# 141004_AriloTX_REV3_1_0_433MHZ_td.net
KiCad netlist of a schematic drawn in EAGLE
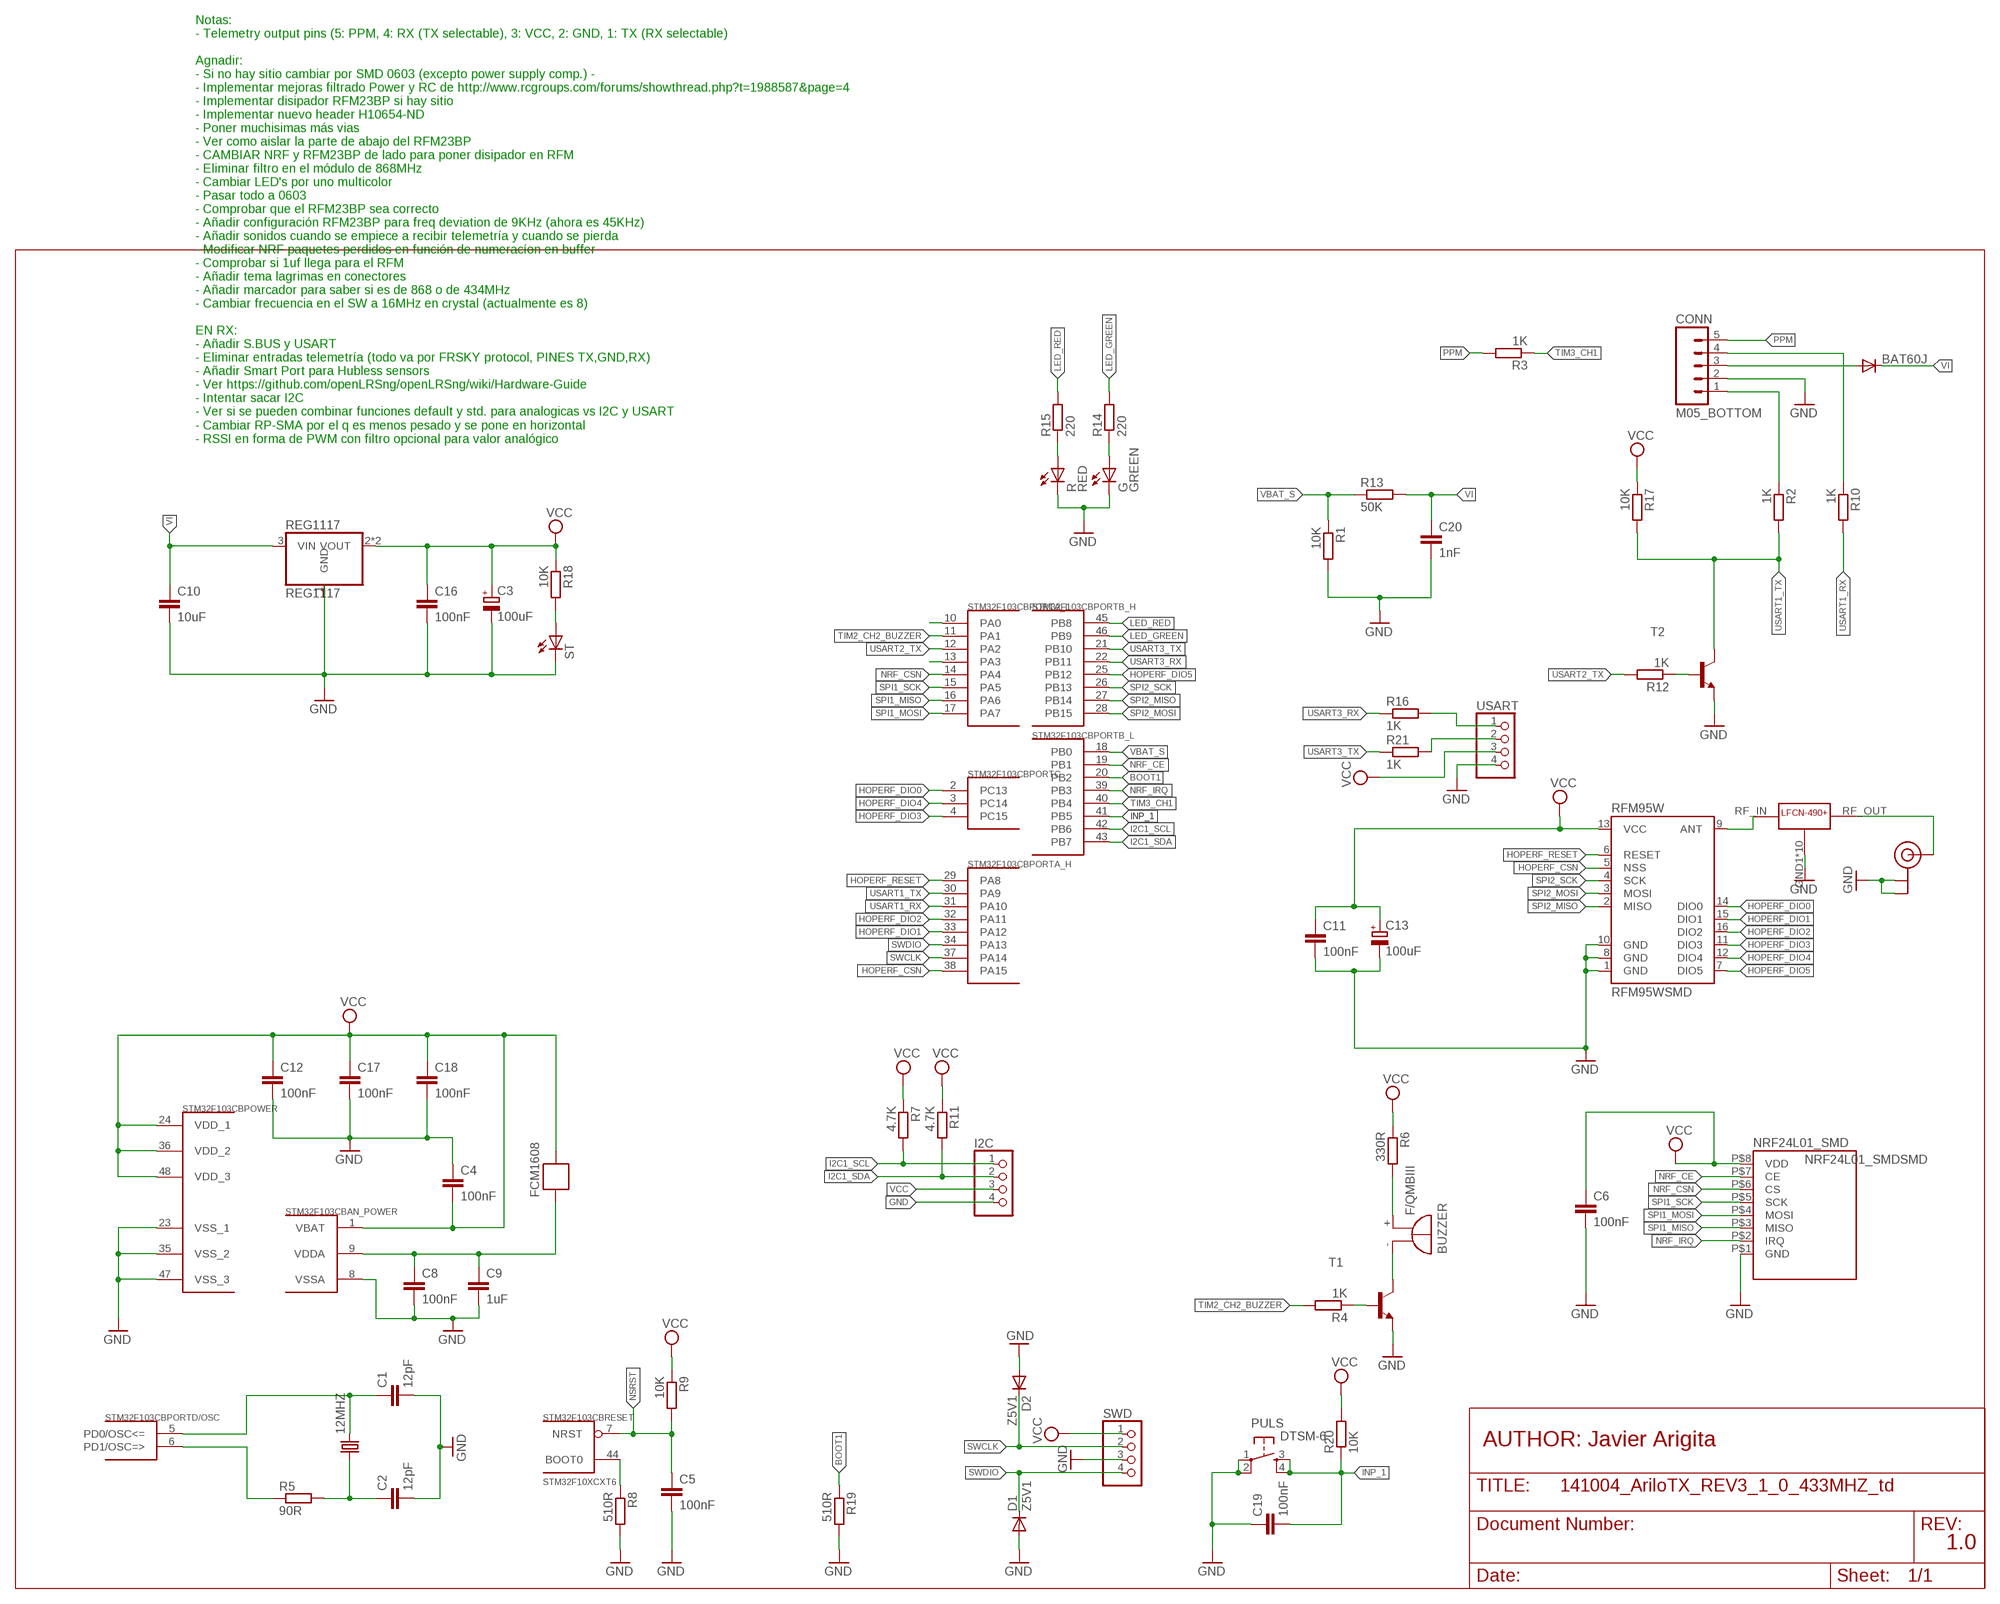
[diagram p0: schematic, sheet 1]

(export (version "E")
  (design (tool "Eeschema 10.0.6"))
  (components
    (comp (ref "12MHZ")
      (value "CRYSTAL5X3")
      (footprint "eagle-import:CRYSTAL-SMD-5X3")
      (libsource (lib "eagle-import") (part "CRYSTAL5X3"))
    )
    (comp (ref "BAT60J")
      (value "DIODE-SOD323-R")
      (footprint "eagle-import:SOD323-R")
      (libsource (lib "eagle-import") (part "DIODE-SOD323-R"))
    )
    (comp (ref "BUZZER")
      (value "F/QMBIII")
      (footprint "eagle-import:F_QMBIII")
      (libsource (lib "eagle-import") (part "F/QMBIII"))
    )
    (comp (ref "C1")
      (value "12pF")
      (footprint "eagle-import:C0603")
      (libsource (lib "eagle-import") (part "C-EUC0603"))
    )
    (comp (ref "C2")
      (value "12pF")
      (footprint "eagle-import:C0603")
      (libsource (lib "eagle-import") (part "C-EUC0603"))
    )
    (comp (ref "C3")
      (value "100uF")
      (footprint "eagle-import:SMC_B")
      (libsource (lib "eagle-import") (part "CPOL-EUSMCB"))
    )
    (comp (ref "C4")
      (value "100nF")
      (footprint "eagle-import:C0603")
      (libsource (lib "eagle-import") (part "C-EUC0603"))
    )
    (comp (ref "C5")
      (value "100nF")
      (footprint "eagle-import:C0603")
      (libsource (lib "eagle-import") (part "C-EUC0603"))
    )
    (comp (ref "C6")
      (value "100nF")
      (footprint "eagle-import:C0603")
      (libsource (lib "eagle-import") (part "C-EUC0603"))
    )
    (comp (ref "C8")
      (value "100nF")
      (footprint "eagle-import:C0603")
      (libsource (lib "eagle-import") (part "C-EUC0603"))
    )
    (comp (ref "C9")
      (value "1uF")
      (footprint "eagle-import:C0603")
      (libsource (lib "eagle-import") (part "C-EUC0603"))
    )
    (comp (ref "C10")
      (value "10uF")
      (footprint "eagle-import:C3216")
      (libsource (lib "eagle-import") (part "resistor_C-EUC3216"))
    )
    (comp (ref "C11")
      (value "100nF")
      (footprint "eagle-import:C0603")
      (libsource (lib "eagle-import") (part "C-EUC0603"))
    )
    (comp (ref "C12")
      (value "100nF")
      (footprint "eagle-import:C0603")
      (libsource (lib "eagle-import") (part "C-EUC0603"))
    )
    (comp (ref "C13")
      (value "100uF")
      (footprint "eagle-import:SMC_B")
      (libsource (lib "eagle-import") (part "CPOL-EUSMCB"))
    )
    (comp (ref "C16")
      (value "100nF")
      (footprint "eagle-import:C0603")
      (libsource (lib "eagle-import") (part "C-EUC0603"))
    )
    (comp (ref "C17")
      (value "100nF")
      (footprint "eagle-import:C0603")
      (libsource (lib "eagle-import") (part "C-EUC0603"))
    )
    (comp (ref "C18")
      (value "100nF")
      (footprint "eagle-import:C0603")
      (libsource (lib "eagle-import") (part "C-EUC0603"))
    )
    (comp (ref "C19")
      (value "100nF")
      (footprint "eagle-import:C0603")
      (libsource (lib "eagle-import") (part "C-EUC0603"))
    )
    (comp (ref "C20")
      (value "1nF")
      (footprint "eagle-import:C0603")
      (libsource (lib "eagle-import") (part "C-EUC0603"))
    )
    (comp (ref "CONN")
      (value "M05_BOTTOM")
      (footprint "eagle-import:M05_BOTTOM")
      (libsource (lib "eagle-import") (part "M05_BOTTOM"))
    )
    (comp (ref "D1")
      (value "Z5V1")
      (footprint "eagle-import:SOD323-R")
      (libsource (lib "eagle-import") (part "DIODE-SOD323-R"))
    )
    (comp (ref "D2")
      (value "Z5V1")
      (footprint "eagle-import:SOD323-R")
      (libsource (lib "eagle-import") (part "DIODE-SOD323-R"))
    )
    (comp (ref "FCM1608")
      (value "FERRITE-BEAD")
      (footprint "eagle-import:R0603")
      (libsource (lib "eagle-import") (part "FERRITE-BEAD"))
    )
    (comp (ref "G")
      (value "GREEN")
      (footprint "eagle-import:CHIP-LED0603")
      (libsource (lib "eagle-import") (part "LEDCHIP-LED0603"))
    )
    (comp (ref "I2C")
      (value "PINHD-1X4")
      (footprint "eagle-import:1X04")
      (libsource (lib "eagle-import") (part "PINHD-1X4"))
    )
    (comp (ref "LFCN490+")
      (value "LFCN490+")
      (footprint "eagle-import:LFCN490+")
      (libsource (lib "eagle-import") (part "LFCN490+"))
    )
    (comp (ref "NRF24L01_SMD")
      (value "NRF24L01_SMDSMD")
      (footprint "eagle-import:NRF24L01_SMD")
      (libsource (lib "eagle-import") (part "NRF24L01_SMDSMD"))
    )
    (comp (ref "PULS")
      (value "DTSM-6")
      (footprint "eagle-import:DTSM-6")
      (libsource (lib "eagle-import") (part "DTSM-6"))
    )
    (comp (ref "R")
      (value "RED")
      (footprint "eagle-import:CHIP-LED0603")
      (libsource (lib "eagle-import") (part "LEDCHIP-LED0603"))
    )
    (comp (ref "R1")
      (value "10K")
      (footprint "eagle-import:R0603")
      (libsource (lib "eagle-import") (part "R-EU_R0603"))
    )
    (comp (ref "R2")
      (value "1K")
      (footprint "eagle-import:R0603")
      (libsource (lib "eagle-import") (part "R-EU_R0603"))
    )
    (comp (ref "R3")
      (value "1K")
      (footprint "eagle-import:R0603")
      (libsource (lib "eagle-import") (part "R-EU_R0603"))
    )
    (comp (ref "R4")
      (value "1K")
      (footprint "eagle-import:R0603")
      (libsource (lib "eagle-import") (part "R-EU_R0603"))
    )
    (comp (ref "R5")
      (value "90R")
      (footprint "eagle-import:R0603")
      (libsource (lib "eagle-import") (part "R-EU_R0603"))
    )
    (comp (ref "R6")
      (value "330R")
      (footprint "eagle-import:R0603")
      (libsource (lib "eagle-import") (part "R-EU_R0603"))
    )
    (comp (ref "R7")
      (value "4.7K")
      (footprint "eagle-import:R0603")
      (libsource (lib "eagle-import") (part "R-EU_R0603"))
    )
    (comp (ref "R8")
      (value "510R")
      (footprint "eagle-import:R0603")
      (libsource (lib "eagle-import") (part "R-EU_R0603"))
    )
    (comp (ref "R9")
      (value "10K")
      (footprint "eagle-import:R0603")
      (libsource (lib "eagle-import") (part "R-EU_R0603"))
    )
    (comp (ref "R10")
      (value "1K")
      (footprint "eagle-import:R0603")
      (libsource (lib "eagle-import") (part "R-EU_R0603"))
    )
    (comp (ref "R11")
      (value "4.7K")
      (footprint "eagle-import:R0603")
      (libsource (lib "eagle-import") (part "R-EU_R0603"))
    )
    (comp (ref "R12")
      (value "1K")
      (footprint "eagle-import:R0603")
      (libsource (lib "eagle-import") (part "R-EU_R0603"))
    )
    (comp (ref "R13")
      (value "50K")
      (footprint "eagle-import:R0603")
      (libsource (lib "eagle-import") (part "R-EU_R0603"))
    )
    (comp (ref "R14")
      (value "220")
      (footprint "eagle-import:R0603")
      (libsource (lib "eagle-import") (part "R-EU_R0603"))
    )
    (comp (ref "R15")
      (value "220")
      (footprint "eagle-import:R0603")
      (libsource (lib "eagle-import") (part "R-EU_R0603"))
    )
    (comp (ref "R16")
      (value "1K")
      (footprint "eagle-import:R0603")
      (libsource (lib "eagle-import") (part "R-EU_R0603"))
    )
    (comp (ref "R17")
      (value "10K")
      (footprint "eagle-import:R0603")
      (libsource (lib "eagle-import") (part "R-EU_R0603"))
    )
    (comp (ref "R18")
      (value "10K")
      (footprint "eagle-import:R0603")
      (libsource (lib "eagle-import") (part "R-EU_R0603"))
    )
    (comp (ref "R19")
      (value "510R")
      (footprint "eagle-import:R0603")
      (libsource (lib "eagle-import") (part "R-EU_R0603"))
    )
    (comp (ref "R20")
      (value "10K")
      (footprint "eagle-import:R0603")
      (libsource (lib "eagle-import") (part "R-EU_R0603"))
    )
    (comp (ref "R21")
      (value "1K")
      (footprint "eagle-import:R0603")
      (libsource (lib "eagle-import") (part "R-EU_R0603"))
    )
    (comp (ref "REG1117")
      (value "REG1117")
      (footprint "eagle-import:SOT223")
      (libsource (lib "eagle-import") (part "REG1117"))
    )
    (comp (ref "RFM95W")
      (value "RFM95WSMD")
      (footprint "eagle-import:MISIEK_RFM95W_SMD")
      (libsource (lib "eagle-import") (part "MISIEK_RFM95WSMD"))
    )
    (comp (ref "ST")
      (value "LEDCHIP-LED0603")
      (footprint "eagle-import:CHIP-LED0603")
      (libsource (lib "eagle-import") (part "LEDCHIP-LED0603"))
    )
    (comp (ref "STM32F103CB")
      (value "STM32F10XCXT6")
      (footprint "eagle-import:TQFP48")
      (libsource (lib "eagle-import") (part "STM32F10XCXT6"))
    )
    (comp (ref "SWD")
      (value "PINHD-1X4")
      (footprint "eagle-import:1X04")
      (libsource (lib "eagle-import") (part "PINHD-1X4"))
    )
    (comp (ref "T1")
      (value "BC848-NPN-SOT23-BEC")
      (footprint "eagle-import:SOT23-BEC")
      (libsource (lib "eagle-import") (part "-NPN-SOT23-BECBC848"))
    )
    (comp (ref "T2")
      (value "BC848-NPN-SOT23-BEC")
      (footprint "eagle-import:SOT23-BEC")
      (libsource (lib "eagle-import") (part "-NPN-SOT23-BECBC848"))
    )
    (comp (ref "U.FL")
      (value "U.FL")
      (footprint "eagle-import:U.FL")
      (libsource (lib "eagle-import") (part "U.FL"))
    )
    (comp (ref "USART")
      (value "PINHD-1X4")
      (footprint "eagle-import:1X04")
      (libsource (lib "eagle-import") (part "PINHD-1X4"))
    )
  )
  (nets
    (net (code "1") (name "BOOT1") (class "Default")
      (node (ref "R19") (pin "1") (pinfunction "1_1") (pintype "passive"))
      (node (ref "STM32F103CB") (pin "20") (pinfunction "PB2_20") (pintype "bidirectional"))
    )
    (net (code "2") (name "GND") (class "Default")
      (node (ref "C1") (pin "2") (pinfunction "2_2") (pintype "passive"))
      (node (ref "C10") (pin "2") (pinfunction "2_2") (pintype "passive"))
      (node (ref "C11") (pin "2") (pinfunction "2_2") (pintype "passive"))
      (node (ref "C12") (pin "2") (pinfunction "2_2") (pintype "passive"))
      (node (ref "C13") (pin "-") (pinfunction "-_-") (pintype "passive"))
      (node (ref "C16") (pin "2") (pinfunction "2_2") (pintype "passive"))
      (node (ref "C17") (pin "2") (pinfunction "2_2") (pintype "passive"))
      (node (ref "C18") (pin "2") (pinfunction "2_2") (pintype "passive"))
      (node (ref "C19") (pin "1") (pinfunction "1_1") (pintype "passive"))
      (node (ref "C2") (pin "2") (pinfunction "2_2") (pintype "passive"))
      (node (ref "C20") (pin "2") (pinfunction "2_2") (pintype "passive"))
      (node (ref "C3") (pin "-") (pinfunction "-_-") (pintype "passive"))
      (node (ref "C4") (pin "1") (pinfunction "1_1") (pintype "passive"))
      (node (ref "C5") (pin "2") (pinfunction "2_2") (pintype "passive"))
      (node (ref "C6") (pin "2") (pinfunction "2_2") (pintype "passive"))
      (node (ref "C8") (pin "2") (pinfunction "2_2") (pintype "passive"))
      (node (ref "C9") (pin "2") (pinfunction "2_2") (pintype "passive"))
      (node (ref "CONN") (pin "2") (pinfunction "2_2") (pintype "passive"))
      (node (ref "D1") (pin "A") (pinfunction "A_A") (pintype "passive"))
      (node (ref "D2") (pin "A") (pinfunction "A_A") (pintype "passive"))
      (node (ref "G") (pin "C") (pinfunction "C_C") (pintype "passive"))
      (node (ref "I2C") (pin "4") (pinfunction "4_4") (pintype "passive"))
      (node (ref "LFCN490+") (pin "GND1") (pinfunction "GND_GND1") (pintype "bidirectional"))
      (node (ref "LFCN490+") (pin "GND10") (pinfunction "GND_GND10") (pintype "bidirectional"))
      (node (ref "LFCN490+") (pin "GND2") (pinfunction "GND_GND2") (pintype "bidirectional"))
      (node (ref "LFCN490+") (pin "GND3") (pinfunction "GND_GND3") (pintype "bidirectional"))
      (node (ref "LFCN490+") (pin "GND4") (pinfunction "GND_GND4") (pintype "bidirectional"))
      (node (ref "LFCN490+") (pin "GND5") (pinfunction "GND_GND5") (pintype "bidirectional"))
      (node (ref "LFCN490+") (pin "GND6") (pinfunction "GND_GND6") (pintype "bidirectional"))
      (node (ref "LFCN490+") (pin "GND7") (pinfunction "GND_GND7") (pintype "bidirectional"))
      (node (ref "LFCN490+") (pin "GND8") (pinfunction "GND_GND8") (pintype "bidirectional"))
      (node (ref "LFCN490+") (pin "GND9") (pinfunction "GND_GND9") (pintype "bidirectional"))
      (node (ref "NRF24L01_SMD") (pin "P$1") (pinfunction "GND_P$1") (pintype "power_in"))
      (node (ref "PULS") (pin "1") (pinfunction "1_1") (pintype "passive"))
      (node (ref "PULS") (pin "2") (pinfunction "2_2") (pintype "passive"))
      (node (ref "R") (pin "C") (pinfunction "C_C") (pintype "passive"))
      (node (ref "R1") (pin "2") (pinfunction "2_2") (pintype "passive"))
      (node (ref "R19") (pin "2") (pinfunction "2_2") (pintype "passive"))
      (node (ref "R8") (pin "2") (pinfunction "2_2") (pintype "passive"))
      (node (ref "REG1117") (pin "1") (pinfunction "GND_1") (pintype "power_in"))
      (node (ref "RFM95W") (pin "1") (pinfunction "GND_1") (pintype "power_in"))
      (node (ref "RFM95W") (pin "10") (pinfunction "GND_10") (pintype "power_in"))
      (node (ref "RFM95W") (pin "8") (pinfunction "GND_8") (pintype "power_in"))
      (node (ref "ST") (pin "C") (pinfunction "C_C") (pintype "passive"))
      (node (ref "STM32F103CB") (pin "23") (pinfunction "VSS_1_23") (pintype "power_in"))
      (node (ref "STM32F103CB") (pin "35") (pinfunction "VSS_2_35") (pintype "power_in"))
      (node (ref "STM32F103CB") (pin "47") (pinfunction "VSS_3_47") (pintype "power_in"))
      (node (ref "STM32F103CB") (pin "8") (pinfunction "VSSA_8") (pintype "power_in"))
      (node (ref "SWD") (pin "3") (pinfunction "3_3") (pintype "passive"))
      (node (ref "T1") (pin "E") (pinfunction "E_E") (pintype "passive"))
      (node (ref "T2") (pin "E") (pinfunction "E_E") (pintype "passive"))
      (node (ref "U.FL") (pin "P$1") (pinfunction "GND_P$1") (pintype "bidirectional"))
      (node (ref "U.FL") (pin "P$2") (pinfunction "GND_P$2") (pintype "bidirectional"))
      (node (ref "USART") (pin "4") (pinfunction "4_4") (pintype "passive"))
    )
    (net (code "3") (name "HOPERF_CSN") (class "Default")
      (node (ref "RFM95W") (pin "5") (pinfunction "NSS_5") (pintype "input"))
      (node (ref "STM32F103CB") (pin "38") (pinfunction "PA15_38") (pintype "bidirectional"))
    )
    (net (code "4") (name "HOPERF_DIO0") (class "Default")
      (node (ref "RFM95W") (pin "14") (pinfunction "DIO0_14") (pintype "input"))
      (node (ref "STM32F103CB") (pin "2") (pinfunction "PC13_2") (pintype "bidirectional"))
    )
    (net (code "5") (name "HOPERF_DIO1") (class "Default")
      (node (ref "RFM95W") (pin "15") (pinfunction "DIO1_15") (pintype "input"))
      (node (ref "STM32F103CB") (pin "33") (pinfunction "PA12_33") (pintype "bidirectional"))
    )
    (net (code "6") (name "HOPERF_DIO2") (class "Default")
      (node (ref "RFM95W") (pin "16") (pinfunction "DIO2_16") (pintype "input"))
      (node (ref "STM32F103CB") (pin "32") (pinfunction "PA11_32") (pintype "bidirectional"))
    )
    (net (code "7") (name "HOPERF_DIO3") (class "Default")
      (node (ref "RFM95W") (pin "11") (pinfunction "DIO3_11") (pintype "bidirectional"))
      (node (ref "STM32F103CB") (pin "4") (pinfunction "PC15_4") (pintype "bidirectional"))
    )
    (net (code "8") (name "HOPERF_DIO4") (class "Default")
      (node (ref "RFM95W") (pin "12") (pinfunction "DIO4_12") (pintype "bidirectional"))
      (node (ref "STM32F103CB") (pin "3") (pinfunction "PC14_3") (pintype "bidirectional"))
    )
    (net (code "9") (name "HOPERF_DIO5") (class "Default")
      (node (ref "RFM95W") (pin "7") (pinfunction "DIO5_7") (pintype "bidirectional"))
      (node (ref "STM32F103CB") (pin "25") (pinfunction "PB12_25") (pintype "bidirectional"))
    )
    (net (code "10") (name "HOPERF_RESET") (class "Default")
      (node (ref "RFM95W") (pin "6") (pinfunction "RESET_6") (pintype "output"))
      (node (ref "STM32F103CB") (pin "29") (pinfunction "PA8_29") (pintype "bidirectional"))
    )
    (net (code "11") (name "I2C1_SCL") (class "Default")
      (node (ref "I2C") (pin "1") (pinfunction "1_1") (pintype "passive"))
      (node (ref "R7") (pin "2") (pinfunction "2_2") (pintype "passive"))
      (node (ref "STM32F103CB") (pin "42") (pinfunction "PB6_42") (pintype "bidirectional"))
    )
    (net (code "12") (name "I2C1_SDA") (class "Default")
      (node (ref "I2C") (pin "2") (pinfunction "2_2") (pintype "passive"))
      (node (ref "R11") (pin "2") (pinfunction "2_2") (pintype "passive"))
      (node (ref "STM32F103CB") (pin "43") (pinfunction "PB7_43") (pintype "bidirectional"))
    )
    (net (code "13") (name "INP_1") (class "Default")
      (node (ref "C19") (pin "2") (pinfunction "2_2") (pintype "passive"))
      (node (ref "PULS") (pin "3") (pinfunction "3_3") (pintype "passive"))
      (node (ref "PULS") (pin "4") (pinfunction "4_4") (pintype "passive"))
      (node (ref "R20") (pin "1") (pinfunction "1_1") (pintype "passive"))
      (node (ref "STM32F103CB") (pin "41") (pinfunction "PB5_41") (pintype "bidirectional"))
    )
    (net (code "14") (name "LED_GREEN") (class "Default")
      (node (ref "R14") (pin "2") (pinfunction "2_2") (pintype "passive"))
      (node (ref "STM32F103CB") (pin "46") (pinfunction "PB9_46") (pintype "bidirectional"))
    )
    (net (code "15") (name "LED_RED") (class "Default")
      (node (ref "R15") (pin "2") (pinfunction "2_2") (pintype "passive"))
      (node (ref "STM32F103CB") (pin "45") (pinfunction "PB8_45") (pintype "bidirectional"))
    )
    (net (code "16") (name "NRF_CE") (class "Default")
      (node (ref "NRF24L01_SMD") (pin "P$7") (pinfunction "CE_P$7") (pintype "input"))
      (node (ref "STM32F103CB") (pin "19") (pinfunction "PB1_19") (pintype "bidirectional"))
    )
    (net (code "17") (name "NRF_CSN") (class "Default")
      (node (ref "NRF24L01_SMD") (pin "P$6") (pinfunction "CS_P$6") (pintype "input"))
      (node (ref "STM32F103CB") (pin "14") (pinfunction "PA4_14") (pintype "bidirectional"))
    )
    (net (code "18") (name "NRF_IRQ") (class "Default")
      (node (ref "NRF24L01_SMD") (pin "P$2") (pinfunction "IRQ_P$2") (pintype "output"))
      (node (ref "STM32F103CB") (pin "39") (pinfunction "PB3_39") (pintype "bidirectional"))
    )
    (net (code "19") (name "NSRST") (class "Default")
      (node (ref "C5") (pin "1") (pinfunction "1_1") (pintype "passive"))
      (node (ref "R9") (pin "2") (pinfunction "2_2") (pintype "passive"))
      (node (ref "STM32F103CB") (pin "7") (pinfunction "NRST_7") (pintype "input"))
    )
    (net (code "20") (name "Net-(12MHZ-2)") (class "Default")
      (node (ref "12MHZ") (pin "3") (pinfunction "2_3") (pintype "passive"))
      (node (ref "C1") (pin "1") (pinfunction "1_1") (pintype "passive"))
      (node (ref "STM32F103CB") (pin "5") (pinfunction "PD0/OSC<=_5") (pintype "bidirectional"))
    )
    (net (code "21") (name "Net-(12MHZ-Pad1)") (class "Default")
      (node (ref "12MHZ") (pin "1") (pinfunction "1_1") (pintype "passive"))
      (node (ref "C2") (pin "1") (pinfunction "1_1") (pintype "passive"))
      (node (ref "R5") (pin "2") (pinfunction "2_2") (pintype "passive"))
    )
    (net (code "22") (name "Net-(BAT60J-PadA)") (class "Default")
      (node (ref "BAT60J") (pin "A") (pinfunction "A_A") (pintype "passive"))
      (node (ref "CONN") (pin "3") (pinfunction "3_3") (pintype "passive"))
    )
    (net (code "23") (name "Net-(BUZZER-+)") (class "Default")
      (node (ref "BUZZER") (pin "-") (pinfunction "+_-") (pintype "passive"))
      (node (ref "T1") (pin "C") (pinfunction "C_C") (pintype "passive"))
    )
    (net (code "24") (name "Net-(BUZZER--)") (class "Default")
      (node (ref "BUZZER") (pin "+") (pinfunction "-_+") (pintype "passive"))
      (node (ref "R6") (pin "2") (pinfunction "2_2") (pintype "passive"))
    )
    (net (code "25") (name "Net-(CONN-Pad1)") (class "Default")
      (node (ref "CONN") (pin "1") (pinfunction "1_1") (pintype "passive"))
      (node (ref "R2") (pin "1") (pinfunction "1_1") (pintype "passive"))
    )
    (net (code "26") (name "Net-(CONN-Pad4)") (class "Default")
      (node (ref "CONN") (pin "4") (pinfunction "4_4") (pintype "passive"))
      (node (ref "R10") (pin "1") (pinfunction "1_1") (pintype "passive"))
    )
    (net (code "27") (name "Net-(FCM1608-P$2)") (class "Default")
      (node (ref "C8") (pin "1") (pinfunction "1_1") (pintype "passive"))
      (node (ref "C9") (pin "1") (pinfunction "1_1") (pintype "passive"))
      (node (ref "FCM1608") (pin "2") (pinfunction "P$2_2") (pintype "bidirectional"))
      (node (ref "STM32F103CB") (pin "9") (pinfunction "VDDA_9") (pintype "power_in"))
    )
    (net (code "28") (name "Net-(G-PadA)") (class "Default")
      (node (ref "G") (pin "A") (pinfunction "A_A") (pintype "passive"))
      (node (ref "R14") (pin "1") (pinfunction "1_1") (pintype "passive"))
    )
    (net (code "29") (name "Net-(LFCN490+-RF_INP)") (class "Default")
      (node (ref "LFCN490+") (pin "RF_IN") (pinfunction "RF_INP_RF_IN") (pintype "bidirectional"))
      (node (ref "RFM95W") (pin "9") (pinfunction "ANT_9") (pintype "bidirectional"))
    )
    (net (code "30") (name "Net-(LFCN490+-RF_OUTP)") (class "Default")
      (node (ref "LFCN490+") (pin "RF_OUT") (pinfunction "RF_OUTP_RF_OUT") (pintype "bidirectional"))
      (node (ref "U.FL") (pin "P$3") (pinfunction "SIGNAL_P$3") (pintype "bidirectional"))
    )
    (net (code "31") (name "Net-(R-PadA)") (class "Default")
      (node (ref "R") (pin "A") (pinfunction "A_A") (pintype "passive"))
      (node (ref "R15") (pin "1") (pinfunction "1_1") (pintype "passive"))
    )
    (net (code "32") (name "Net-(R4-Pad1)") (class "Default")
      (node (ref "R4") (pin "1") (pinfunction "1_1") (pintype "passive"))
      (node (ref "T1") (pin "B") (pinfunction "B_B") (pintype "passive"))
    )
    (net (code "33") (name "Net-(R12-Pad1)") (class "Default")
      (node (ref "R12") (pin "1") (pinfunction "1_1") (pintype "passive"))
      (node (ref "T2") (pin "B") (pinfunction "B_B") (pintype "passive"))
    )
    (net (code "34") (name "Net-(R16-Pad2)") (class "Default")
      (node (ref "R16") (pin "2") (pinfunction "2_2") (pintype "passive"))
      (node (ref "USART") (pin "1") (pinfunction "1_1") (pintype "passive"))
    )
    (net (code "35") (name "Net-(R18-Pad2)") (class "Default")
      (node (ref "R18") (pin "2") (pinfunction "2_2") (pintype "passive"))
      (node (ref "ST") (pin "A") (pinfunction "A_A") (pintype "passive"))
    )
    (net (code "36") (name "Net-(R21-Pad2)") (class "Default")
      (node (ref "R21") (pin "2") (pinfunction "2_2") (pintype "passive"))
      (node (ref "USART") (pin "2") (pinfunction "2_2") (pintype "passive"))
    )
    (net (code "37") (name "Net-(STM32F103CBG-PD1{slash}OSC=>)") (class "Default")
      (node (ref "R5") (pin "1") (pinfunction "1_1") (pintype "passive"))
      (node (ref "STM32F103CB") (pin "6") (pinfunction "PD1/OSC=>_6") (pintype "bidirectional"))
    )
    (net (code "38") (name "Net-(STM32F103CBI-BOOT0)") (class "Default")
      (node (ref "R8") (pin "1") (pinfunction "1_1") (pintype "passive"))
      (node (ref "STM32F103CB") (pin "44") (pinfunction "BOOT0_44") (pintype "input"))
    )
    (net (code "39") (name "PPM") (class "Default")
      (node (ref "CONN") (pin "5") (pinfunction "5_5") (pintype "passive"))
      (node (ref "R3") (pin "2") (pinfunction "2_2") (pintype "passive"))
    )
    (net (code "40") (name "SPI1_MISO") (class "Default")
      (node (ref "NRF24L01_SMD") (pin "P$3") (pinfunction "MISO_P$3") (pintype "output"))
      (node (ref "STM32F103CB") (pin "16") (pinfunction "PA6_16") (pintype "bidirectional"))
    )
    (net (code "41") (name "SPI1_MOSI") (class "Default")
      (node (ref "NRF24L01_SMD") (pin "P$4") (pinfunction "MOSI_P$4") (pintype "input"))
      (node (ref "STM32F103CB") (pin "17") (pinfunction "PA7_17") (pintype "bidirectional"))
    )
    (net (code "42") (name "SPI1_SCK") (class "Default")
      (node (ref "NRF24L01_SMD") (pin "P$5") (pinfunction "SCK_P$5") (pintype "input"))
      (node (ref "STM32F103CB") (pin "15") (pinfunction "PA5_15") (pintype "bidirectional"))
    )
    (net (code "43") (name "SPI2_MISO") (class "Default")
      (node (ref "RFM95W") (pin "2") (pinfunction "MISO_2") (pintype "output"))
      (node (ref "STM32F103CB") (pin "27") (pinfunction "PB14_27") (pintype "bidirectional"))
    )
    (net (code "44") (name "SPI2_MOSI") (class "Default")
      (node (ref "RFM95W") (pin "3") (pinfunction "MOSI_3") (pintype "input"))
      (node (ref "STM32F103CB") (pin "28") (pinfunction "PB15_28") (pintype "bidirectional"))
    )
    (net (code "45") (name "SPI2_SCK") (class "Default")
      (node (ref "RFM95W") (pin "4") (pinfunction "SCK_4") (pintype "input"))
      (node (ref "STM32F103CB") (pin "26") (pinfunction "PB13_26") (pintype "bidirectional"))
    )
    (net (code "46") (name "SWCLK") (class "Default")
      (node (ref "D2") (pin "C") (pinfunction "C_C") (pintype "passive"))
      (node (ref "STM32F103CB") (pin "37") (pinfunction "PA14_37") (pintype "bidirectional"))
      (node (ref "SWD") (pin "2") (pinfunction "2_2") (pintype "passive"))
    )
    (net (code "47") (name "SWDIO") (class "Default")
      (node (ref "D1") (pin "C") (pinfunction "C_C") (pintype "passive"))
      (node (ref "STM32F103CB") (pin "34") (pinfunction "PA13_34") (pintype "bidirectional"))
      (node (ref "SWD") (pin "4") (pinfunction "4_4") (pintype "passive"))
    )
    (net (code "48") (name "TIM2_CH2_BUZZER") (class "Default")
      (node (ref "R4") (pin "2") (pinfunction "2_2") (pintype "passive"))
      (node (ref "STM32F103CB") (pin "11") (pinfunction "PA1_11") (pintype "bidirectional"))
    )
    (net (code "49") (name "TIM3_CH1") (class "Default")
      (node (ref "R3") (pin "1") (pinfunction "1_1") (pintype "passive"))
      (node (ref "STM32F103CB") (pin "40") (pinfunction "PB4_40") (pintype "bidirectional"))
    )
    (net (code "50") (name "USART1_RX") (class "Default")
      (node (ref "R10") (pin "2") (pinfunction "2_2") (pintype "passive"))
      (node (ref "STM32F103CB") (pin "31") (pinfunction "PA10_31") (pintype "bidirectional"))
    )
    (net (code "51") (name "USART1_TX") (class "Default")
      (node (ref "R17") (pin "2") (pinfunction "2_2") (pintype "passive"))
      (node (ref "R2") (pin "2") (pinfunction "2_2") (pintype "passive"))
      (node (ref "STM32F103CB") (pin "30") (pinfunction "PA9_30") (pintype "bidirectional"))
      (node (ref "T2") (pin "C") (pinfunction "C_C") (pintype "passive"))
    )
    (net (code "52") (name "USART2_TX") (class "Default")
      (node (ref "R12") (pin "2") (pinfunction "2_2") (pintype "passive"))
      (node (ref "STM32F103CB") (pin "12") (pinfunction "PA2_12") (pintype "bidirectional"))
    )
    (net (code "53") (name "USART3_RX") (class "Default")
      (node (ref "R16") (pin "1") (pinfunction "1_1") (pintype "passive"))
      (node (ref "STM32F103CB") (pin "22") (pinfunction "PB11_22") (pintype "bidirectional"))
    )
    (net (code "54") (name "USART3_TX") (class "Default")
      (node (ref "R21") (pin "1") (pinfunction "1_1") (pintype "passive"))
      (node (ref "STM32F103CB") (pin "21") (pinfunction "PB10_21") (pintype "bidirectional"))
    )
    (net (code "55") (name "VBAT_S") (class "Default")
      (node (ref "R1") (pin "1") (pinfunction "1_1") (pintype "passive"))
      (node (ref "R13") (pin "1") (pinfunction "1_1") (pintype "passive"))
      (node (ref "STM32F103CB") (pin "18") (pinfunction "PB0_18") (pintype "bidirectional"))
    )
    (net (code "56") (name "VCC") (class "Default")
      (node (ref "C11") (pin "1") (pinfunction "1_1") (pintype "passive"))
      (node (ref "C12") (pin "1") (pinfunction "1_1") (pintype "passive"))
      (node (ref "C13") (pin "+") (pinfunction "+_+") (pintype "passive"))
      (node (ref "C16") (pin "1") (pinfunction "1_1") (pintype "passive"))
      (node (ref "C17") (pin "1") (pinfunction "1_1") (pintype "passive"))
      (node (ref "C18") (pin "1") (pinfunction "1_1") (pintype "passive"))
      (node (ref "C3") (pin "+") (pinfunction "+_+") (pintype "passive"))
      (node (ref "C4") (pin "2") (pinfunction "2_2") (pintype "passive"))
      (node (ref "C6") (pin "1") (pinfunction "1_1") (pintype "passive"))
      (node (ref "FCM1608") (pin "1") (pinfunction "P$1_1") (pintype "bidirectional"))
      (node (ref "I2C") (pin "3") (pinfunction "3_3") (pintype "passive"))
      (node (ref "NRF24L01_SMD") (pin "P$8") (pinfunction "VDD_P$8") (pintype "bidirectional"))
      (node (ref "R11") (pin "1") (pinfunction "1_1") (pintype "passive"))
      (node (ref "R17") (pin "1") (pinfunction "1_1") (pintype "passive"))
      (node (ref "R18") (pin "1") (pinfunction "1_1") (pintype "passive"))
      (node (ref "R20") (pin "2") (pinfunction "2_2") (pintype "passive"))
      (node (ref "R6") (pin "1") (pinfunction "1_1") (pintype "passive"))
      (node (ref "R7") (pin "1") (pinfunction "1_1") (pintype "passive"))
      (node (ref "R9") (pin "1") (pinfunction "1_1") (pintype "passive"))
      (node (ref "REG1117") (pin "2") (pinfunction "VOUT_2") (pintype "power_in"))
      (node (ref "REG1117") (pin "4") (pinfunction "VOUT_4") (pintype "power_in"))
      (node (ref "RFM95W") (pin "13") (pinfunction "VCC_13") (pintype "bidirectional"))
      (node (ref "STM32F103CB") (pin "1") (pinfunction "VBAT_1") (pintype "power_in"))
      (node (ref "STM32F103CB") (pin "24") (pinfunction "VDD_1_24") (pintype "power_in"))
      (node (ref "STM32F103CB") (pin "36") (pinfunction "VDD_2_36") (pintype "power_in"))
      (node (ref "STM32F103CB") (pin "48") (pinfunction "VDD_3_48") (pintype "power_in"))
      (node (ref "SWD") (pin "1") (pinfunction "1_1") (pintype "passive"))
      (node (ref "USART") (pin "3") (pinfunction "3_3") (pintype "passive"))
    )
    (net (code "57") (name "VI") (class "Default")
      (node (ref "BAT60J") (pin "C") (pinfunction "C_C") (pintype "passive"))
      (node (ref "C10") (pin "1") (pinfunction "1_1") (pintype "passive"))
      (node (ref "C20") (pin "1") (pinfunction "1_1") (pintype "passive"))
      (node (ref "R13") (pin "2") (pinfunction "2_2") (pintype "passive"))
      (node (ref "REG1117") (pin "3") (pinfunction "VIN_3") (pintype "input"))
    )
    (net (code "58") (name "unconnected-(STM32F103CBC-PA0-Pad10)") (class "Default")
      (node (ref "STM32F103CB") (pin "10") (pinfunction "PA0_10") (pintype "bidirectional"))
    )
    (net (code "59") (name "unconnected-(STM32F103CBC-PA3-Pad13)") (class "Default")
      (node (ref "STM32F103CB") (pin "13") (pinfunction "PA3_13") (pintype "bidirectional"))
    )
  )
)
